# Power.net
KiCad netlist of a schematic drawn in Altium Designer
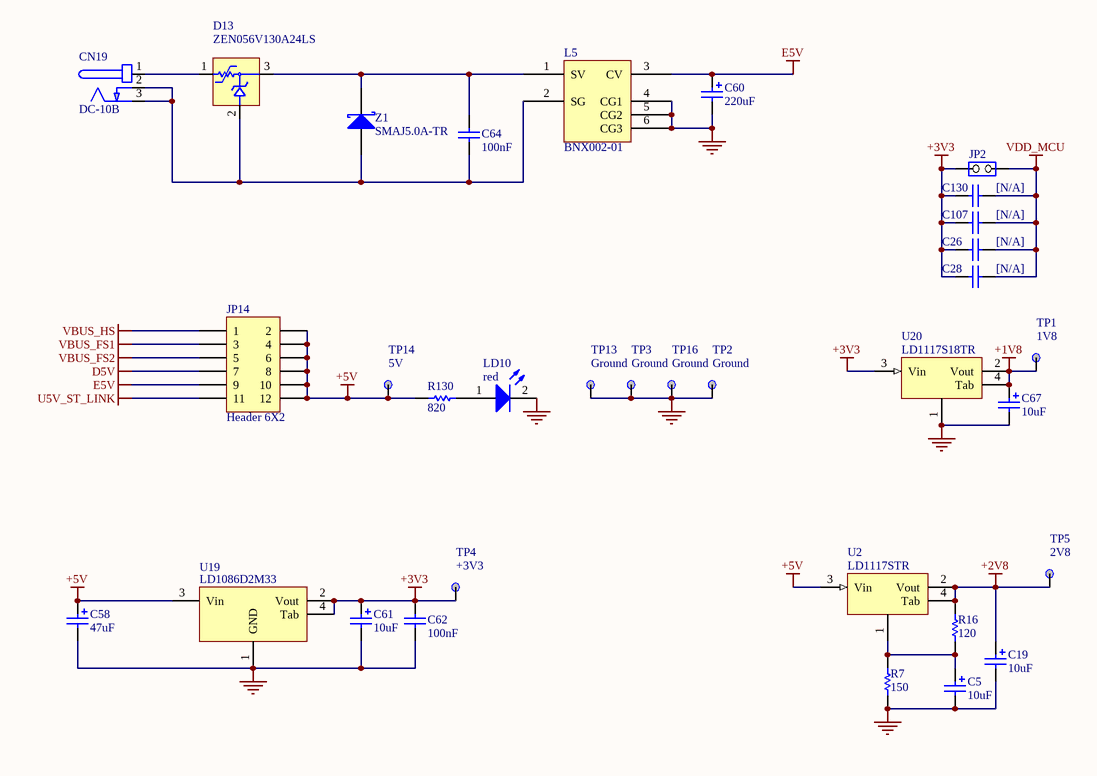
[diagram p0: Power.SchDoc]

(export (version "E")
  (design (tool "Eeschema 10.0.6"))
  (components
    (comp (ref "C5")
      (value "10uF")
      (footprint "TAN-A")
      (description "Polarized Capacitor (Radial)")
      (fields (field (name "PUBLISHER") "Altium Limited"))
      (libsource (lib "Miscellaneous Devices") (part "Cap Pol1"))
    )
    (comp (ref "C19")
      (value "10uF")
      (footprint "TAN-A")
      (description "Polarized Capacitor (Radial)")
      (fields (field (name "PUBLISHER") "Altium Limited"))
      (libsource (lib "Miscellaneous Devices") (part "Cap Pol1"))
    )
    (comp (ref "C26")
      (value "[N/A]")
      (footprint "0603C")
      (description "Capacitor")
      (fields (field (name "PUBLISHER") "Altium Limited"))
      (libsource (lib "Miscellaneous Devices") (part "Cap"))
    )
    (comp (ref "C28")
      (value "[N/A]")
      (footprint "0603C")
      (description "Capacitor")
      (fields (field (name "PUBLISHER") "Altium Limited"))
      (libsource (lib "Miscellaneous Devices") (part "Cap"))
    )
    (comp (ref "C58")
      (value "47uF")
      (footprint "CAE_5R3X5R3_H5R4")
      (description "Polarized Capacitor (Radial)")
      (fields (field (name "PUBLISHER") "Altium Limited"))
      (libsource (lib "Miscellaneous Devices") (part "Cap Pol1"))
    )
    (comp (ref "C60")
      (value "220uF")
      (footprint "c310m-6")
      (description "Polarized Capacitor (Radial)")
      (fields (field (name "PUBLISHER") "Altium Limited"))
      (libsource (lib "Miscellaneous Devices") (part "Cap Pol1"))
    )
    (comp (ref "C61")
      (value "10uF")
      (footprint "TAN-A")
      (description "Polarized Capacitor (Radial)")
      (fields (field (name "PUBLISHER") "Altium Limited"))
      (libsource (lib "Miscellaneous Devices") (part "Cap Pol1"))
    )
    (comp (ref "C62")
      (value "100nF")
      (footprint "0603C")
      (description "Capacitor")
      (fields (field (name "PUBLISHER") "Altium Limited"))
      (libsource (lib "Miscellaneous Devices") (part "Cap"))
    )
    (comp (ref "C64")
      (value "100nF")
      (footprint "0603C")
      (description "Capacitor")
      (fields (field (name "PUBLISHER") "Altium Limited"))
      (libsource (lib "Miscellaneous Devices") (part "CAP"))
    )
    (comp (ref "C67")
      (value "10uF")
      (footprint "TAN-A")
      (description "Polarized Capacitor (Radial)")
      (fields (field (name "PUBLISHER") "Altium Limited"))
      (libsource (lib "Miscellaneous Devices") (part "Cap Pol1"))
    )
    (comp (ref "C107")
      (value "[N/A]")
      (footprint "0603C")
      (description "Capacitor")
      (fields (field (name "PUBLISHER") "Altium Limited"))
      (libsource (lib "Miscellaneous Devices") (part "Cap"))
    )
    (comp (ref "C130")
      (value "[N/A]")
      (footprint "0603C")
      (description "Capacitor")
      (fields (field (name "PUBLISHER") "Altium Limited"))
      (libsource (lib "Miscellaneous Devices") (part "Cap"))
    )
    (comp (ref "CN19")
      (value "DC-10B")
      (footprint "PWR_JACK_DC10")
      (libsource (lib "STR910_SCHLIB") (part "PJ202A"))
    )
    (comp (ref "D13")
      (value "ZEN056V130A24LS")
      (footprint "TYCO_ZEN056V130A24LS")
      (libsource (lib "STR910_SCHLIB") (part "ZEN056V130A24LS"))
    )
    (comp (ref "JP2") (value "~") (footprint "SIP2") (libsource (lib "*") (part "JP2")))
    (comp (ref "JP14")
      (value "Header 6X2")
      (footprint "HDR_2X6_2R54")
      (description "Header, 6-Pin, Dual row")
      (fields (field (name "PUBLISHER") "Altium Limited"))
      (libsource (lib "mb1045") (part "Header 6X2"))
    )
    (comp (ref "L5")
      (value "BNX002-01")
      (footprint "BNX001")
      (libsource (lib "STR910_SCHLIB") (part "BNX002"))
    )
    (comp (ref "LD10")
      (value "red")
      (footprint "0603D")
      (description "Typical RED, GREEN, YELLOW, AMBER GaAs LED")
      (fields (field (name "PUBLISHER") "Altium Limited"))
      (libsource (lib "Miscellaneous Devices") (part "LED2"))
    )
    (comp (ref "R7")
      (value "150")
      (footprint "0603R")
      (description "Resistor")
      (fields (field (name "PUBLISHER") "Altium Limited"))
      (libsource (lib "Miscellaneous Devices") (part "res1"))
    )
    (comp (ref "R16")
      (value "120")
      (footprint "0603R")
      (description "Resistor")
      (fields (field (name "PUBLISHER") "Altium Limited"))
      (libsource (lib "Miscellaneous Devices") (part "res1"))
    )
    (comp (ref "R130")
      (value "820")
      (footprint "0603R")
      (description "Resistor")
      (fields (field (name "PUBLISHER") "Altium Limited"))
      (libsource (lib "Miscellaneous Devices") (part "res1"))
    )
    (comp (ref "TP1") (value "1V8") (footprint "TP") (libsource (lib "*") (part "TP")))
    (comp (ref "TP2") (value "Ground") (footprint "TP") (libsource (lib "*") (part "TP")))
    (comp (ref "TP3") (value "Ground") (footprint "TP") (libsource (lib "*") (part "TP")))
    (comp (ref "TP4") (value "+3V3") (footprint "TP") (libsource (lib "*") (part "TP")))
    (comp (ref "TP5") (value "2V8") (footprint "TP") (libsource (lib "*") (part "TP")))
    (comp (ref "TP13") (value "Ground") (footprint "TP") (libsource (lib "*") (part "TP")))
    (comp (ref "TP14") (value "5V") (footprint "TP") (libsource (lib "*") (part "TP")))
    (comp (ref "TP16") (value "Ground") (footprint "TP") (libsource (lib "*") (part "TP")))
    (comp (ref "U2") (value "LD1117STR") (footprint "SOT-223") (libsource (lib "mb1045") (part "LD1117")))
    (comp (ref "U19")
      (value "LD1086D2M33")
      (footprint "TO263-3")
      (libsource (lib "mb1045") (part "VOLTREG1"))
    )
    (comp (ref "U20") (value "LD1117S18TR") (footprint "SOT-223") (libsource (lib "mb1045") (part "LD1117")))
    (comp (ref "Z1")
      (value "SMAJ5.0A-TR")
      (footprint "sma")
      (description "Schottky Diode")
      (fields (field (name "PUBLISHER") "Altium Limited"))
      (libsource (lib "Miscellaneous Devices") (part "D Schottky"))
    )
  )
  (nets
    (net (code "1") (name "+1V8") (class "Default")
      (node (ref "C67") (pin "1") (pinfunction "1_1") (pintype "passive"))
      (node (ref "TP1") (pin "1") (pinfunction "1_1") (pintype "passive"))
      (node (ref "U20") (pin "2") (pinfunction "Vout_2") (pintype "power_in"))
      (node (ref "U20") (pin "4") (pinfunction "Tab_4") (pintype "power_in"))
    )
    (net (code "2") (name "+2V8") (class "Default")
      (node (ref "C19") (pin "1") (pinfunction "1_1") (pintype "passive"))
      (node (ref "R16") (pin "1") (pinfunction "1_1") (pintype "passive"))
      (node (ref "TP5") (pin "1") (pinfunction "1_1") (pintype "passive"))
      (node (ref "U2") (pin "2") (pinfunction "Vout_2") (pintype "power_in"))
      (node (ref "U2") (pin "4") (pinfunction "Tab_4") (pintype "power_in"))
    )
    (net (code "3") (name "+3V3") (class "Default")
      (node (ref "C107") (pin "1") (pinfunction "1_1") (pintype "passive"))
      (node (ref "C130") (pin "1") (pinfunction "1_1") (pintype "passive"))
      (node (ref "C26") (pin "1") (pinfunction "1_1") (pintype "passive"))
      (node (ref "C28") (pin "1") (pinfunction "1_1") (pintype "passive"))
      (node (ref "C61") (pin "1") (pinfunction "1_1") (pintype "passive"))
      (node (ref "C62") (pin "1") (pinfunction "1_1") (pintype "passive"))
      (node (ref "JP2") (pin "1") (pinfunction "COMMON_1") (pintype "passive"))
      (node (ref "TP4") (pin "1") (pinfunction "1_1") (pintype "passive"))
      (node (ref "U19") (pin "2") (pinfunction "Vout_2") (pintype "passive"))
      (node (ref "U19") (pin "4") (pinfunction "Tab_4") (pintype "passive"))
      (node (ref "U20") (pin "3") (pinfunction "Vin_3") (pintype "input"))
    )
    (net (code "4") (name "+5V") (class "Default")
      (node (ref "C58") (pin "1") (pinfunction "1_1") (pintype "passive"))
      (node (ref "JP14") (pin "10") (pinfunction "10_10") (pintype "passive"))
      (node (ref "JP14") (pin "12") (pinfunction "12_12") (pintype "passive"))
      (node (ref "JP14") (pin "2") (pinfunction "2_2") (pintype "passive"))
      (node (ref "JP14") (pin "4") (pinfunction "4_4") (pintype "passive"))
      (node (ref "JP14") (pin "6") (pinfunction "6_6") (pintype "passive"))
      (node (ref "JP14") (pin "8") (pinfunction "8_8") (pintype "passive"))
      (node (ref "R130") (pin "2") (pinfunction "2_2") (pintype "passive"))
      (node (ref "TP14") (pin "1") (pinfunction "1_1") (pintype "passive"))
      (node (ref "U19") (pin "3") (pinfunction "Vin_3") (pintype "passive"))
      (node (ref "U2") (pin "3") (pinfunction "Vin_3") (pintype "input"))
    )
    (net (code "5") (name "D5V") (class "Default")
      (node (ref "JP14") (pin "7") (pinfunction "7_7") (pintype "passive"))
    )
    (net (code "6") (name "E5V") (class "Default")
      (node (ref "C60") (pin "1") (pinfunction "1_1") (pintype "passive"))
      (node (ref "JP14") (pin "9") (pinfunction "9_9") (pintype "passive"))
      (node (ref "L5") (pin "3") (pinfunction "CV_3") (pintype "passive"))
    )
    (net (code "7") (name "GND") (class "Default")
      (node (ref "C19") (pin "2") (pinfunction "2_2") (pintype "passive"))
      (node (ref "C5") (pin "2") (pinfunction "2_2") (pintype "passive"))
      (node (ref "C58") (pin "2") (pinfunction "2_2") (pintype "passive"))
      (node (ref "C60") (pin "2") (pinfunction "2_2") (pintype "passive"))
      (node (ref "C61") (pin "2") (pinfunction "2_2") (pintype "passive"))
      (node (ref "C62") (pin "2") (pinfunction "2_2") (pintype "passive"))
      (node (ref "C67") (pin "2") (pinfunction "2_2") (pintype "passive"))
      (node (ref "L5") (pin "4") (pinfunction "CG1_4") (pintype "passive"))
      (node (ref "L5") (pin "5") (pinfunction "CG2_5") (pintype "passive"))
      (node (ref "L5") (pin "6") (pinfunction "CG3_6") (pintype "passive"))
      (node (ref "LD10") (pin "2") (pinfunction "K_2") (pintype "passive"))
      (node (ref "R7") (pin "2") (pinfunction "2_2") (pintype "passive"))
      (node (ref "TP13") (pin "1") (pinfunction "1_1") (pintype "passive"))
      (node (ref "TP16") (pin "1") (pinfunction "1_1") (pintype "passive"))
      (node (ref "TP2") (pin "1") (pinfunction "1_1") (pintype "passive"))
      (node (ref "TP3") (pin "1") (pinfunction "1_1") (pintype "passive"))
      (node (ref "U19") (pin "1") (pinfunction "GND_1") (pintype "passive"))
      (node (ref "U20") (pin "1") (pintype "passive"))
    )
    (net (code "8") (name "Net-(C5-Pad1)") (class "Default")
      (node (ref "C5") (pin "1") (pinfunction "1_1") (pintype "passive"))
      (node (ref "R16") (pin "2") (pinfunction "2_2") (pintype "passive"))
      (node (ref "R7") (pin "1") (pinfunction "1_1") (pintype "passive"))
      (node (ref "U2") (pin "1") (pintype "passive"))
    )
    (net (code "9") (name "Net-(CN19-+)") (class "Default")
      (node (ref "CN19") (pin "1") (pinfunction "+_1") (pintype "passive"))
      (node (ref "D13") (pin "1") (pintype "passive"))
    )
    (net (code "10") (name "Net-(L5-SG)") (class "Default")
      (node (ref "C64") (pin "2") (pinfunction "2_2") (pintype "passive"))
      (node (ref "CN19") (pin "2") (pinfunction "GND_2") (pintype "passive"))
      (node (ref "CN19") (pin "3") (pinfunction "GND_3") (pintype "passive"))
      (node (ref "D13") (pin "2") (pintype "passive"))
      (node (ref "L5") (pin "2") (pinfunction "SG_2") (pintype "passive"))
      (node (ref "Z1") (pin "1") (pinfunction "A_1") (pintype "passive"))
    )
    (net (code "11") (name "Net-(L5-SV)") (class "Default")
      (node (ref "C64") (pin "1") (pinfunction "1_1") (pintype "passive"))
      (node (ref "D13") (pin "3") (pintype "passive"))
      (node (ref "L5") (pin "1") (pinfunction "SV_1") (pintype "passive"))
      (node (ref "Z1") (pin "2") (pinfunction "K_2") (pintype "passive"))
    )
    (net (code "12") (name "Net-(LD10-A)") (class "Default")
      (node (ref "LD10") (pin "1") (pinfunction "A_1") (pintype "passive"))
      (node (ref "R130") (pin "1") (pinfunction "1_1") (pintype "passive"))
    )
    (net (code "13") (name "U5V_ST_LINK") (class "Default")
      (node (ref "JP14") (pin "11") (pinfunction "11_11") (pintype "passive"))
    )
    (net (code "14") (name "VBUS_FS1") (class "Default")
      (node (ref "JP14") (pin "3") (pinfunction "3_3") (pintype "passive"))
    )
    (net (code "15") (name "VBUS_FS2") (class "Default")
      (node (ref "JP14") (pin "5") (pinfunction "5_5") (pintype "passive"))
    )
    (net (code "16") (name "VBUS_HS") (class "Default")
      (node (ref "JP14") (pin "1") (pinfunction "1_1") (pintype "passive"))
    )
    (net (code "17") (name "VDD_MCU") (class "Default")
      (node (ref "C107") (pin "2") (pinfunction "2_2") (pintype "passive"))
      (node (ref "C130") (pin "2") (pinfunction "2_2") (pintype "passive"))
      (node (ref "C26") (pin "2") (pinfunction "2_2") (pintype "passive"))
      (node (ref "C28") (pin "2") (pinfunction "2_2") (pintype "passive"))
      (node (ref "JP2") (pin "2") (pinfunction "NO_2") (pintype "passive"))
    )
  )
)
